# MXR3_v1.net
KiCad netlist of a schematic drawn in EAGLE
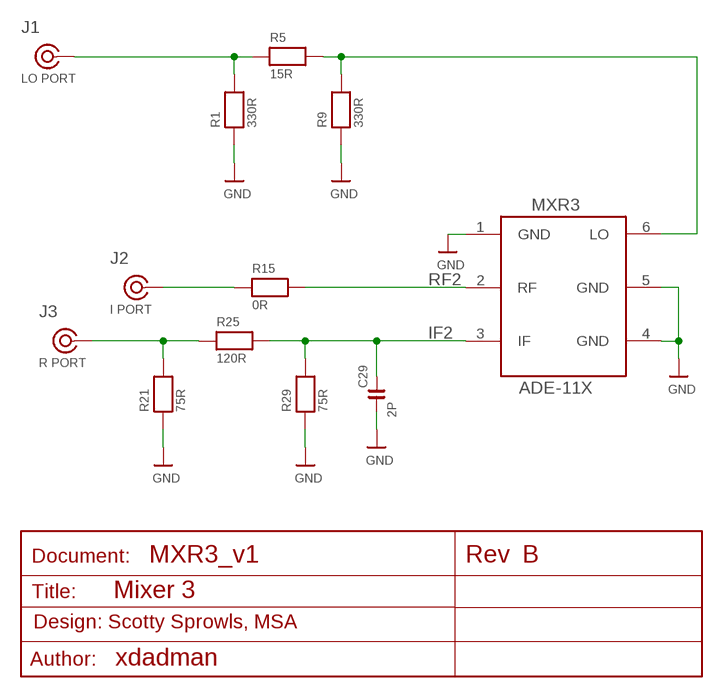
[diagram p0: schematic, sheet 1]

(export (version "E")
  (design (tool "Eeschema 10.0.6"))
  (components
    (comp (ref "C29")
      (value "2P")
      (footprint "eagle-import:C0603")
      (libsource (lib "eagle-import") (part "CC06032P"))
    )
    (comp (ref "J1")
      (value "LO PORT")
      (footprint "eagle-import:SLIM_COAX_PAD")
      (libsource (lib "eagle-import") (part "COAX"))
    )
    (comp (ref "J2")
      (value "I PORT")
      (footprint "eagle-import:SLIM_COAX_PAD")
      (libsource (lib "eagle-import") (part "COAX"))
    )
    (comp (ref "J3")
      (value "R PORT")
      (footprint "eagle-import:SLIM_COAX_PAD")
      (libsource (lib "eagle-import") (part "COAX"))
    )
    (comp (ref "MXR3")
      (value "ADE-11X")
      (footprint "eagle-import:ADE-11X")
      (libsource (lib "eagle-import") (part "ADE-11X"))
    )
    (comp (ref "R1")
      (value "330R")
      (footprint "eagle-import:R0805")
      (libsource (lib "eagle-import") (part "R0805330R"))
    )
    (comp (ref "R5")
      (value "15R")
      (footprint "eagle-import:0805")
      (libsource (lib "eagle-import") (part "R080515R"))
    )
    (comp (ref "R9")
      (value "330R")
      (footprint "eagle-import:R0805")
      (libsource (lib "eagle-import") (part "R0805330R"))
    )
    (comp (ref "R15")
      (value "0R")
      (footprint "eagle-import:R0805")
      (libsource (lib "eagle-import") (part "R08050R"))
    )
    (comp (ref "R21")
      (value "75R")
      (footprint "eagle-import:R0805")
      (libsource (lib "eagle-import") (part "R080575R"))
    )
    (comp (ref "R25")
      (value "120R")
      (footprint "eagle-import:R0805")
      (libsource (lib "eagle-import") (part "R0805120R"))
    )
    (comp (ref "R29")
      (value "75R")
      (footprint "eagle-import:R0805")
      (libsource (lib "eagle-import") (part "R080575R"))
    )
  )
  (nets
    (net (code "1") (name "/IF2") (class "Default")
      (node (ref "C29") (pin "2") (pinfunction "2_2") (pintype "passive"))
      (node (ref "MXR3") (pin "3") (pinfunction "IF_3") (pintype "bidirectional"))
      (node (ref "R25") (pin "2") (pinfunction "2_2") (pintype "passive"))
      (node (ref "R29") (pin "2") (pinfunction "2_2") (pintype "passive"))
    )
    (net (code "2") (name "/RF2") (class "Default")
      (node (ref "MXR3") (pin "2") (pinfunction "RF_2") (pintype "bidirectional"))
      (node (ref "R15") (pin "2") (pinfunction "2_2") (pintype "passive"))
    )
    (net (code "3") (name "GND") (class "Default")
      (node (ref "C29") (pin "1") (pinfunction "1_1") (pintype "passive"))
      (node (ref "MXR3") (pin "1") (pinfunction "GND_1") (pintype "bidirectional"))
      (node (ref "MXR3") (pin "4") (pinfunction "GND_4") (pintype "bidirectional"))
      (node (ref "MXR3") (pin "5") (pinfunction "GND_5") (pintype "bidirectional"))
      (node (ref "R1") (pin "1") (pinfunction "1_1") (pintype "passive"))
      (node (ref "R21") (pin "1") (pinfunction "1_1") (pintype "passive"))
      (node (ref "R29") (pin "1") (pinfunction "1_1") (pintype "passive"))
      (node (ref "R9") (pin "1") (pinfunction "1_1") (pintype "passive"))
    )
    (net (code "4") (name "Net-(J1A-1)") (class "Default")
      (node (ref "J1") (pin "SIG") (pinfunction "1_SIG") (pintype "passive"))
      (node (ref "R1") (pin "2") (pinfunction "2_2") (pintype "passive"))
      (node (ref "R5") (pin "1") (pinfunction "1_1") (pintype "passive"))
    )
    (net (code "5") (name "Net-(J2A-1)") (class "Default")
      (node (ref "J2") (pin "SIG") (pinfunction "1_SIG") (pintype "passive"))
      (node (ref "R15") (pin "1") (pinfunction "1_1") (pintype "passive"))
    )
    (net (code "6") (name "Net-(J3A-1)") (class "Default")
      (node (ref "J3") (pin "SIG") (pinfunction "1_SIG") (pintype "passive"))
      (node (ref "R21") (pin "2") (pinfunction "2_2") (pintype "passive"))
      (node (ref "R25") (pin "1") (pinfunction "1_1") (pintype "passive"))
    )
    (net (code "7") (name "Net-(MXR3-LO)") (class "Default")
      (node (ref "MXR3") (pin "6") (pinfunction "LO_6") (pintype "bidirectional"))
      (node (ref "R5") (pin "2") (pinfunction "2_2") (pintype "passive"))
      (node (ref "R9") (pin "2") (pinfunction "2_2") (pintype "passive"))
    )
  )
)
